# LM324.net
KiCad netlist of a schematic drawn in Altium Designer
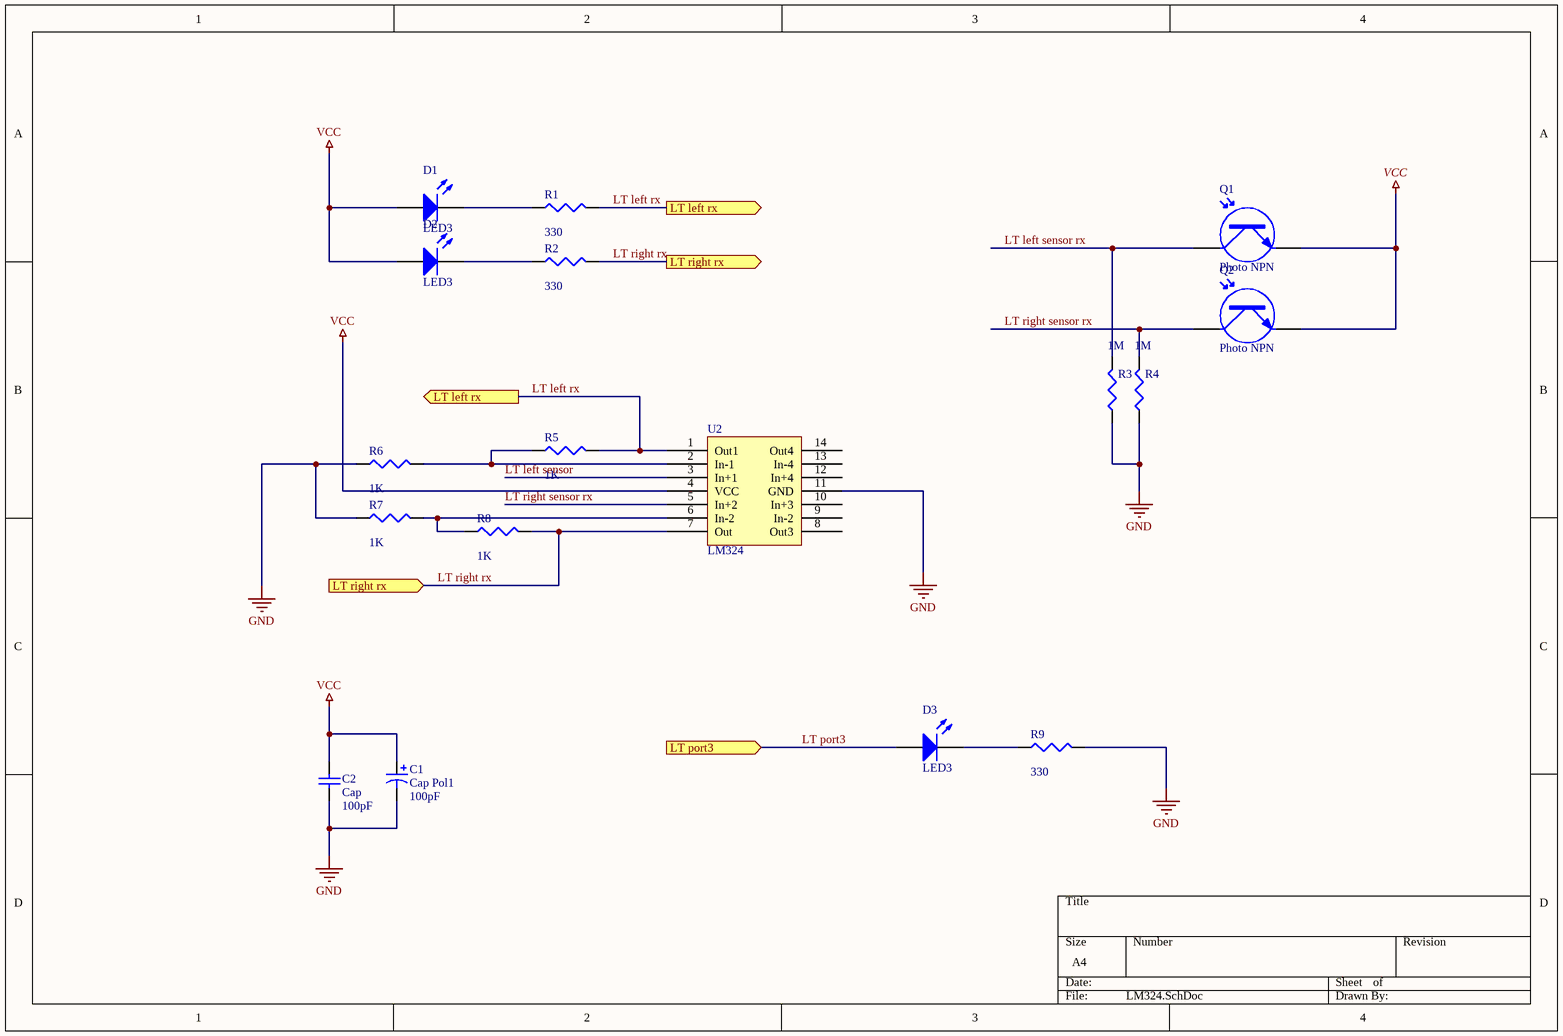
[diagram p0: LM324.SchDoc]

(export (version "E")
  (design (tool "Eeschema 10.0.6"))
  (components
    (comp (ref "C1")
      (value "Cap Pol1")
      (footprint "RB7.6-15")
      (description "Polarized Capacitor (Radial)")
      (fields (field (name "ALTIUM_VALUE") "100pF") (field (name "PUBLISHER") "Altium Limited"))
      (libsource (lib "Miscellaneous+Devices") (part "Cap Pol1"))
    )
    (comp (ref "C2")
      (value "Cap")
      (footprint "RAD-0.3")
      (description "Capacitor")
      (fields (field (name "ALTIUM_VALUE") "100pF") (field (name "PUBLISHER") "Altium Limited"))
      (libsource (lib "Miscellaneous+Devices") (part "Cap"))
    )
    (comp (ref "D1")
      (value "LED3")
      (footprint "3.5X2.8X1.9")
      (description "Typical BLUE SiC LED")
      (fields (field (name "PUBLISHER") "Altium Limited"))
      (libsource (lib "Miscellaneous+Devices") (part "LED3"))
    )
    (comp (ref "D2")
      (value "LED3")
      (footprint "3.5X2.8X1.9")
      (description "Typical BLUE SiC LED")
      (fields (field (name "PUBLISHER") "Altium Limited"))
      (libsource (lib "Miscellaneous+Devices") (part "LED3"))
    )
    (comp (ref "D3")
      (value "LED3")
      (footprint "3.5X2.8X1.9")
      (description "Typical BLUE SiC LED")
      (fields (field (name "PUBLISHER") "Altium Limited"))
      (libsource (lib "Miscellaneous+Devices") (part "LED3"))
    )
    (comp (ref "Q1")
      (value "Photo NPN")
      (footprint "TO-220_A")
      (description "NPN Phototransistor")
      (fields (field (name "PUBLISHER") "Altium Limited"))
      (libsource (lib "Miscellaneous+Devices") (part "Photo NPN"))
    )
    (comp (ref "Q2")
      (value "Photo NPN")
      (footprint "TO-220_A")
      (description "NPN Phototransistor")
      (fields (field (name "PUBLISHER") "Altium Limited"))
      (libsource (lib "Miscellaneous+Devices") (part "Photo NPN"))
    )
    (comp (ref "R1")
      (value "330")
      (footprint "J1-0603")
      (description "Resistor")
      (fields (field (name "Comment") "Res3") (field (name "PUBLISHER") "Altium Limited"))
      (libsource (lib "Miscellaneous+Devices") (part "Res3"))
    )
    (comp (ref "R2")
      (value "330")
      (footprint "J1-0603")
      (description "Resistor")
      (fields (field (name "Comment") "Res3") (field (name "PUBLISHER") "Altium Limited"))
      (libsource (lib "Miscellaneous+Devices") (part "Res3"))
    )
    (comp (ref "R3")
      (value "1M")
      (footprint "J1-0603")
      (description "Resistor")
      (fields (field (name "Comment") "Res3") (field (name "PUBLISHER") "Altium Limited"))
      (libsource (lib "Miscellaneous+Devices") (part "Res3"))
    )
    (comp (ref "R4")
      (value "1M")
      (footprint "J1-0603")
      (description "Resistor")
      (fields (field (name "Comment") "Res3") (field (name "PUBLISHER") "Altium Limited"))
      (libsource (lib "Miscellaneous+Devices") (part "Res3"))
    )
    (comp (ref "R5")
      (value "1K")
      (footprint "J1-0603")
      (description "Resistor")
      (fields (field (name "Comment") "Res3") (field (name "PUBLISHER") "Altium Limited"))
      (libsource (lib "Miscellaneous+Devices") (part "Res3"))
    )
    (comp (ref "R6")
      (value "1K")
      (footprint "J1-0603")
      (description "Resistor")
      (fields (field (name "Comment") "Res3") (field (name "PUBLISHER") "Altium Limited"))
      (libsource (lib "Miscellaneous+Devices") (part "Res3"))
    )
    (comp (ref "R7")
      (value "1K")
      (footprint "J1-0603")
      (description "Resistor")
      (fields (field (name "Comment") "Res3") (field (name "PUBLISHER") "Altium Limited"))
      (libsource (lib "Miscellaneous+Devices") (part "Res3"))
    )
    (comp (ref "R8")
      (value "1K")
      (footprint "J1-0603")
      (description "Resistor")
      (fields (field (name "Comment") "Res3") (field (name "PUBLISHER") "Altium Limited"))
      (libsource (lib "Miscellaneous+Devices") (part "Res3"))
    )
    (comp (ref "R9")
      (value "330")
      (footprint "J1-0603")
      (description "Resistor")
      (fields (field (name "Comment") "Res3") (field (name "PUBLISHER") "Altium Limited"))
      (libsource (lib "Miscellaneous+Devices") (part "Res3"))
    )
    (comp (ref "U2") (value "LM324") (footprint "SOT27-1") (libsource (lib "PICO_sch") (part "LM324")))
  )
  (nets
    (net (code "1") (name "/LT left rx") (class "Default")
      (node (ref "R1") (pin "2") (pinfunction "2_2") (pintype "passive"))
      (node (ref "R5") (pin "2") (pinfunction "2_2") (pintype "passive"))
      (node (ref "U2") (pin "1") (pinfunction "Out1_1") (pintype "passive"))
    )
    (net (code "2") (name "/LT left sensor") (class "Default")
      (node (ref "U2") (pin "3") (pinfunction "In+1_3") (pintype "passive"))
    )
    (net (code "3") (name "/LT left sensor rx") (class "Default")
      (node (ref "Q1") (pin "1") (pinfunction "C_1") (pintype "passive"))
      (node (ref "R3") (pin "2") (pinfunction "2_2") (pintype "passive"))
    )
    (net (code "4") (name "/LT port3") (class "Default")
      (node (ref "D3") (pin "1") (pinfunction "A_1") (pintype "passive"))
    )
    (net (code "5") (name "/LT right rx") (class "Default")
      (node (ref "R2") (pin "2") (pinfunction "2_2") (pintype "passive"))
      (node (ref "R8") (pin "2") (pinfunction "2_2") (pintype "passive"))
      (node (ref "U2") (pin "7") (pinfunction "Out_7") (pintype "passive"))
    )
    (net (code "6") (name "/LT right sensor rx") (class "Default")
      (node (ref "Q2") (pin "1") (pinfunction "C_1") (pintype "passive"))
      (node (ref "R4") (pin "2") (pinfunction "2_2") (pintype "passive"))
      (node (ref "U2") (pin "5") (pinfunction "In+2_5") (pintype "passive"))
    )
    (net (code "7") (name "GND") (class "Default")
      (node (ref "C1") (pin "2") (pinfunction "2_2") (pintype "passive"))
      (node (ref "C2") (pin "1") (pinfunction "1_1") (pintype "passive"))
      (node (ref "R3") (pin "1") (pinfunction "1_1") (pintype "passive"))
      (node (ref "R4") (pin "1") (pinfunction "1_1") (pintype "passive"))
      (node (ref "R6") (pin "1") (pinfunction "1_1") (pintype "passive"))
      (node (ref "R7") (pin "1") (pinfunction "1_1") (pintype "passive"))
      (node (ref "R9") (pin "2") (pinfunction "2_2") (pintype "passive"))
      (node (ref "U2") (pin "11") (pinfunction "GND_11") (pintype "passive"))
    )
    (net (code "8") (name "Net-(D1-K)") (class "Default")
      (node (ref "D1") (pin "2") (pinfunction "K_2") (pintype "passive"))
      (node (ref "R1") (pin "1") (pinfunction "1_1") (pintype "passive"))
    )
    (net (code "9") (name "Net-(D2-K)") (class "Default")
      (node (ref "D2") (pin "2") (pinfunction "K_2") (pintype "passive"))
      (node (ref "R2") (pin "1") (pinfunction "1_1") (pintype "passive"))
    )
    (net (code "10") (name "Net-(D3-K)") (class "Default")
      (node (ref "D3") (pin "2") (pinfunction "K_2") (pintype "passive"))
      (node (ref "R9") (pin "1") (pinfunction "1_1") (pintype "passive"))
    )
    (net (code "11") (name "Net-(R7-Pad2)") (class "Default")
      (node (ref "R7") (pin "2") (pinfunction "2_2") (pintype "passive"))
      (node (ref "R8") (pin "1") (pinfunction "1_1") (pintype "passive"))
      (node (ref "U2") (pin "6") (pinfunction "In-2_6") (pintype "passive"))
    )
    (net (code "12") (name "Net-(U2-In-1)") (class "Default")
      (node (ref "R5") (pin "1") (pinfunction "1_1") (pintype "passive"))
      (node (ref "R6") (pin "2") (pinfunction "2_2") (pintype "passive"))
      (node (ref "U2") (pin "2") (pinfunction "In-1_2") (pintype "passive"))
    )
    (net (code "13") (name "VCC") (class "Default")
      (node (ref "C1") (pin "1") (pinfunction "1_1") (pintype "passive"))
      (node (ref "C2") (pin "2") (pinfunction "2_2") (pintype "passive"))
      (node (ref "D1") (pin "1") (pinfunction "A_1") (pintype "passive"))
      (node (ref "D2") (pin "1") (pinfunction "A_1") (pintype "passive"))
      (node (ref "Q1") (pin "3") (pinfunction "E_3") (pintype "passive"))
      (node (ref "Q2") (pin "3") (pinfunction "E_3") (pintype "passive"))
      (node (ref "U2") (pin "4") (pinfunction "VCC_4") (pintype "passive"))
    )
    (net (code "14") (name "unconnected-(U2-In+3-Pad10)") (class "Default")
      (node (ref "U2") (pin "10") (pinfunction "In+3_10") (pintype "passive"))
    )
    (net (code "15") (name "unconnected-(U2-In+4-Pad12)") (class "Default")
      (node (ref "U2") (pin "12") (pinfunction "In+4_12") (pintype "passive"))
    )
    (net (code "16") (name "unconnected-(U2-In-2-Pad9)") (class "Default")
      (node (ref "U2") (pin "9") (pinfunction "In-2_9") (pintype "passive"))
    )
    (net (code "17") (name "unconnected-(U2-In-4-Pad13)") (class "Default")
      (node (ref "U2") (pin "13") (pinfunction "In-4_13") (pintype "passive"))
    )
    (net (code "18") (name "unconnected-(U2-Out3-Pad8)") (class "Default")
      (node (ref "U2") (pin "8") (pinfunction "Out3_8") (pintype "passive"))
    )
    (net (code "19") (name "unconnected-(U2-Out4-Pad14)") (class "Default")
      (node (ref "U2") (pin "14") (pinfunction "Out4_14") (pintype "passive"))
    )
  )
)
